# hs-64-spi_rev1_0.net
KiCad netlist of a schematic drawn in EAGLE
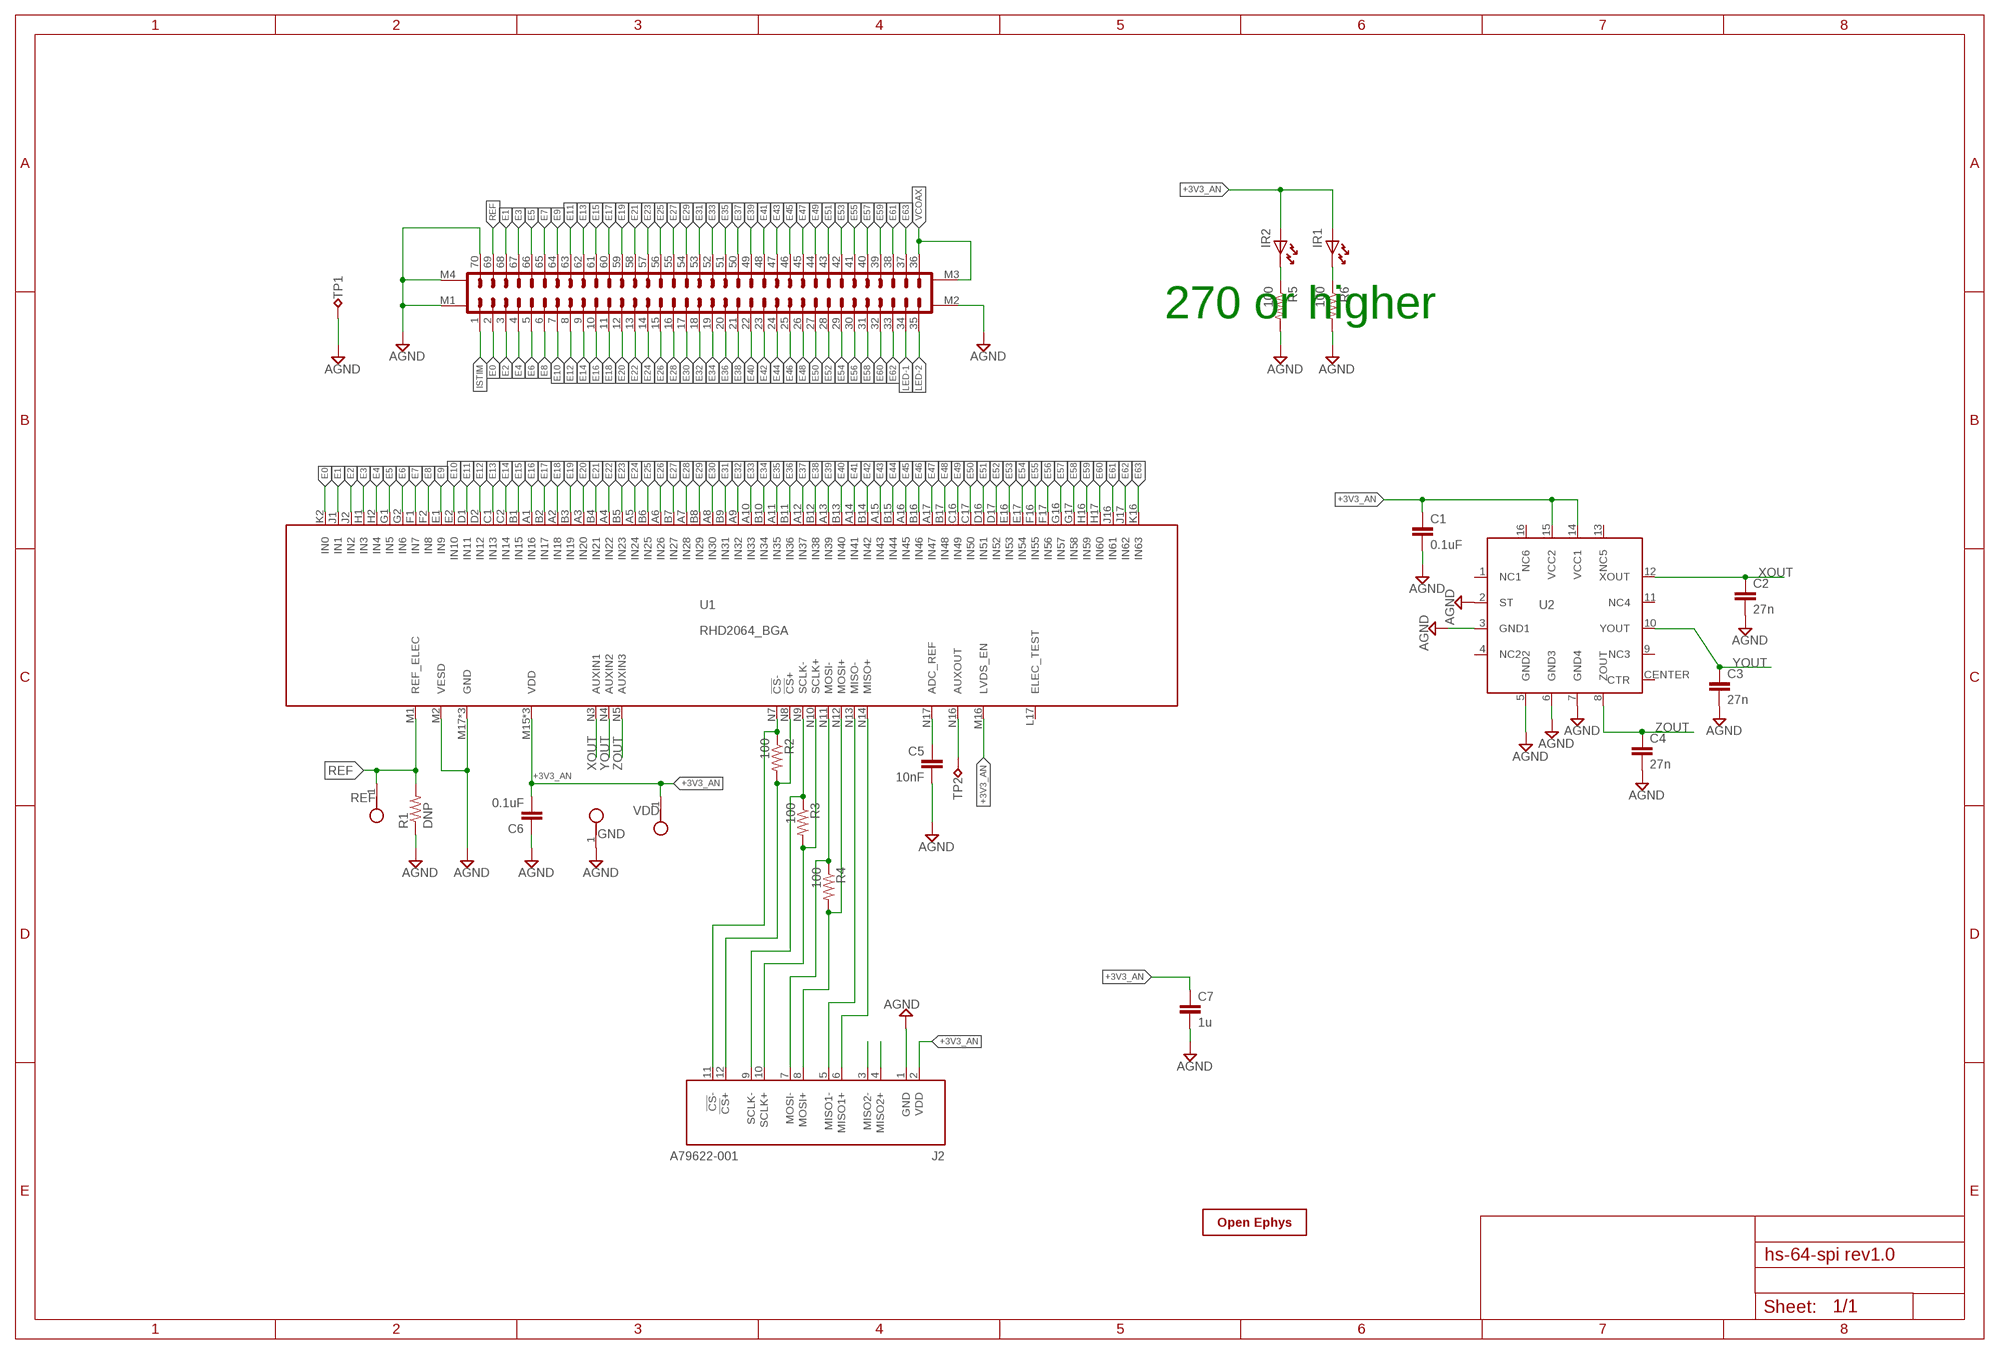
[diagram p0: schematic, sheet 1]

(export (version "E")
  (design (tool "Eeschema 10.0.6"))
  (components
    (comp (ref "C1")
      (value "0.1uF")
      (footprint "eagle-import:0402")
      (libsource (lib "eagle-import") (part "C_0402"))
    )
    (comp (ref "C2")
      (value "27n")
      (footprint "eagle-import:0402")
      (libsource (lib "eagle-import") (part "C_0402"))
    )
    (comp (ref "C3")
      (value "27n")
      (footprint "eagle-import:0402")
      (libsource (lib "eagle-import") (part "C_0402"))
    )
    (comp (ref "C4")
      (value "27n")
      (footprint "eagle-import:0402")
      (libsource (lib "eagle-import") (part "C_0402"))
    )
    (comp (ref "C5")
      (value "10nF")
      (footprint "eagle-import:0402T")
      (fields (field (name "PARTNO") "GRM033R71E103KE14D"))
      (libsource (lib "eagle-import") (part "C_0402T"))
    )
    (comp (ref "C6")
      (value "0.1uF")
      (footprint "eagle-import:0402T")
      (libsource (lib "eagle-import") (part "C_0402T"))
    )
    (comp (ref "C7")
      (value "1u")
      (footprint "eagle-import:0402")
      (libsource (lib "eagle-import") (part "C_0402"))
    )
    (comp (ref "GND")
      (value "TESTPOINT_SMALL")
      (footprint "eagle-import:TESTPOINT_SMALL")
      (libsource (lib "eagle-import") (part "TESTPOINT_SMALL"))
    )
    (comp (ref "IR1")
      (value "LEDHAND")
      (footprint "eagle-import:LED_HAND")
      (libsource (lib "eagle-import") (part "LEDHAND"))
    )
    (comp (ref "IR2")
      (value "LEDHAND")
      (footprint "eagle-import:LED_HAND")
      (libsource (lib "eagle-import") (part "LEDHAND"))
    )
    (comp (ref "J1")
      (value "DF40C-70DP-0.4V(51)")
      (footprint "eagle-import:DF40-70HEAD-LESS-SILK")
      (libsource (lib "eagle-import") (part "PINHD-2X35+4DF40-70HEAD-LESS-SILK"))
    )
    (comp (ref "J2")
      (value "A79622-001")
      (footprint "eagle-import:A79622-001")
      (libsource (lib "eagle-import") (part "A79622-001"))
    )
    (comp (ref "R1")
      (value "DNP")
      (footprint "eagle-import:0603")
      (fields (field (name "MPN") "ERJ-3EKFxxxxV"))
      (libsource (lib "eagle-import") (part "R_0603"))
    )
    (comp (ref "R2")
      (value "100")
      (footprint "eagle-import:0402")
      (libsource (lib "eagle-import") (part "R_0402"))
    )
    (comp (ref "R3")
      (value "100")
      (footprint "eagle-import:0402")
      (libsource (lib "eagle-import") (part "R_0402"))
    )
    (comp (ref "R4")
      (value "100")
      (footprint "eagle-import:0402")
      (libsource (lib "eagle-import") (part "R_0402"))
    )
    (comp (ref "R5")
      (value "100")
      (footprint "eagle-import:0402")
      (libsource (lib "eagle-import") (part "R_0402"))
    )
    (comp (ref "R6")
      (value "100")
      (footprint "eagle-import:0402")
      (libsource (lib "eagle-import") (part "R_0402"))
    )
    (comp (ref "REF")
      (value "TESTPOINT_SMALL")
      (footprint "eagle-import:TESTPOINT_SMALL")
      (libsource (lib "eagle-import") (part "TESTPOINT_SMALL"))
    )
    (comp (ref "TP1")
      (value "VCC")
      (footprint "eagle-import:TP07R")
      (libsource (lib "eagle-import") (part "TPTP07R"))
    )
    (comp (ref "TP2")
      (value "VCC")
      (footprint "eagle-import:TP07R")
      (libsource (lib "eagle-import") (part "TPTP07R"))
    )
    (comp (ref "U1")
      (value "RHD2064_BGA")
      (footprint "eagle-import:BGA104_0.5MM")
      (libsource (lib "eagle-import") (part "RHD2164_BGA_BGA"))
    )
    (comp (ref "U2")
      (value "ADXL335_IDAX")
      (footprint "eagle-import:ADXL335_IDAX")
      (libsource (lib "eagle-import") (part "ADXL335_IDAX"))
    )
    (comp (ref "VDD")
      (value "TESTPOINT_SMALL")
      (footprint "eagle-import:TESTPOINT_SMALL")
      (libsource (lib "eagle-import") (part "TESTPOINT_SMALL"))
    )
    (comp (ref "X")
      (value "OE-LOGO_3.5X2.5")
      (footprint "eagle-import:OE-LOGO-3.5X2.5")
      (libsource (lib "eagle-import") (part "OE-LOGO_3.5X2.5"))
    )
  )
  (nets
    (net (code "1") (name "+3V3_AN") (class "Default")
      (node (ref "C1") (pin "1") (pinfunction "1_1") (pintype "passive"))
      (node (ref "C6") (pin "2") (pinfunction "2_2") (pintype "passive"))
      (node (ref "C7") (pin "1") (pinfunction "1_1") (pintype "passive"))
      (node (ref "IR1") (pin "A") (pinfunction "A_A") (pintype "bidirectional"))
      (node (ref "IR2") (pin "A") (pinfunction "A_A") (pintype "bidirectional"))
      (node (ref "J2") (pin "2") (pinfunction "VDD_2") (pintype "bidirectional"))
      (node (ref "U1") (pin "M15") (pinfunction "VDD_M15") (pintype "power_in"))
      (node (ref "U1") (pin "M16") (pinfunction "LVDS_EN_M16") (pintype "input"))
      (node (ref "U1") (pin "N15") (pinfunction "VDD_N15") (pintype "power_in"))
      (node (ref "U1") (pin "N2") (pinfunction "VDD_N2") (pintype "power_in"))
      (node (ref "U2") (pin "14") (pinfunction "VCC1_14") (pintype "power_in"))
      (node (ref "U2") (pin "15") (pinfunction "VCC2_15") (pintype "power_in"))
      (node (ref "VDD") (pin "1") (pinfunction "1_1") (pintype "passive"))
    )
    (net (code "2") (name "/XOUT") (class "Default")
      (node (ref "C2") (pin "1") (pinfunction "1_1") (pintype "passive"))
      (node (ref "U1") (pin "N3") (pinfunction "AUXIN1_N3") (pintype "input"))
      (node (ref "U2") (pin "12") (pinfunction "XOUT_12") (pintype "output"))
    )
    (net (code "3") (name "/YOUT") (class "Default")
      (node (ref "C3") (pin "1") (pinfunction "1_1") (pintype "passive"))
      (node (ref "U1") (pin "N4") (pinfunction "AUXIN2_N4") (pintype "input"))
      (node (ref "U2") (pin "10") (pinfunction "YOUT_10") (pintype "output"))
    )
    (net (code "4") (name "/ZOUT") (class "Default")
      (node (ref "C4") (pin "1") (pinfunction "1_1") (pintype "passive"))
      (node (ref "U1") (pin "N5") (pinfunction "AUXIN3_N5") (pintype "input"))
      (node (ref "U2") (pin "8") (pinfunction "ZOUT_8") (pintype "output"))
    )
    (net (code "5") (name "AGND") (class "Default")
      (node (ref "C1") (pin "2") (pinfunction "2_2") (pintype "passive"))
      (node (ref "C2") (pin "2") (pinfunction "2_2") (pintype "passive"))
      (node (ref "C3") (pin "2") (pinfunction "2_2") (pintype "passive"))
      (node (ref "C4") (pin "2") (pinfunction "2_2") (pintype "passive"))
      (node (ref "C5") (pin "2") (pinfunction "2_2") (pintype "passive"))
      (node (ref "C6") (pin "1") (pinfunction "1_1") (pintype "passive"))
      (node (ref "C7") (pin "2") (pinfunction "2_2") (pintype "passive"))
      (node (ref "GND") (pin "1") (pinfunction "1_1") (pintype "passive"))
      (node (ref "J1") (pin "70") (pinfunction "70_70") (pintype "bidirectional"))
      (node (ref "J1") (pin "M1") (pinfunction "M1_M1") (pintype "bidirectional"))
      (node (ref "J1") (pin "M2") (pinfunction "M2_M2") (pintype "bidirectional"))
      (node (ref "J1") (pin "M4") (pinfunction "M4_M4") (pintype "bidirectional"))
      (node (ref "J2") (pin "1") (pinfunction "GND_1") (pintype "power_in"))
      (node (ref "R1") (pin "1") (pinfunction "1_1") (pintype "passive"))
      (node (ref "R5") (pin "2") (pinfunction "2_2") (pintype "passive"))
      (node (ref "R6") (pin "2") (pinfunction "2_2") (pintype "passive"))
      (node (ref "TP1") (pin "TP") (pinfunction "TP_TP") (pintype "bidirectional"))
      (node (ref "U1") (pin "M17") (pinfunction "GND_M17") (pintype "power_in"))
      (node (ref "U1") (pin "M2") (pinfunction "VESD_M2") (pintype "power_in"))
      (node (ref "U1") (pin "N1") (pinfunction "GND_N1") (pintype "power_in"))
      (node (ref "U1") (pin "N6") (pinfunction "GND_N6") (pintype "power_in"))
      (node (ref "U2") (pin "2") (pinfunction "ST_2") (pintype "input"))
      (node (ref "U2") (pin "3") (pinfunction "GND1_3") (pintype "power_in"))
      (node (ref "U2") (pin "5") (pinfunction "GND2_5") (pintype "power_in"))
      (node (ref "U2") (pin "6") (pinfunction "GND3_6") (pintype "power_in"))
      (node (ref "U2") (pin "7") (pinfunction "GND4_7") (pintype "power_in"))
    )
    (net (code "6") (name "E0") (class "Default")
      (node (ref "J1") (pin "2") (pinfunction "2_2") (pintype "bidirectional"))
      (node (ref "U1") (pin "K2") (pinfunction "IN0_K2") (pintype "input"))
    )
    (net (code "7") (name "E1") (class "Default")
      (node (ref "J1") (pin "68") (pinfunction "68_68") (pintype "bidirectional"))
      (node (ref "U1") (pin "J1") (pinfunction "IN1_J1") (pintype "input"))
    )
    (net (code "8") (name "E2") (class "Default")
      (node (ref "J1") (pin "3") (pinfunction "3_3") (pintype "bidirectional"))
      (node (ref "U1") (pin "J2") (pinfunction "IN2_J2") (pintype "input"))
    )
    (net (code "9") (name "E3") (class "Default")
      (node (ref "J1") (pin "67") (pinfunction "67_67") (pintype "bidirectional"))
      (node (ref "U1") (pin "H1") (pinfunction "IN3_H1") (pintype "input"))
    )
    (net (code "10") (name "E4") (class "Default")
      (node (ref "J1") (pin "4") (pinfunction "4_4") (pintype "bidirectional"))
      (node (ref "U1") (pin "H2") (pinfunction "IN4_H2") (pintype "input"))
    )
    (net (code "11") (name "E5") (class "Default")
      (node (ref "J1") (pin "66") (pinfunction "66_66") (pintype "bidirectional"))
      (node (ref "U1") (pin "G1") (pinfunction "IN5_G1") (pintype "input"))
    )
    (net (code "12") (name "E6") (class "Default")
      (node (ref "J1") (pin "5") (pinfunction "5_5") (pintype "bidirectional"))
      (node (ref "U1") (pin "G2") (pinfunction "IN6_G2") (pintype "input"))
    )
    (net (code "13") (name "E7") (class "Default")
      (node (ref "J1") (pin "65") (pinfunction "65_65") (pintype "bidirectional"))
      (node (ref "U1") (pin "F1") (pinfunction "IN7_F1") (pintype "input"))
    )
    (net (code "14") (name "E8") (class "Default")
      (node (ref "J1") (pin "6") (pinfunction "6_6") (pintype "bidirectional"))
      (node (ref "U1") (pin "F2") (pinfunction "IN8_F2") (pintype "input"))
    )
    (net (code "15") (name "E9") (class "Default")
      (node (ref "J1") (pin "64") (pinfunction "64_64") (pintype "bidirectional"))
      (node (ref "U1") (pin "E1") (pinfunction "IN9_E1") (pintype "input"))
    )
    (net (code "16") (name "E10") (class "Default")
      (node (ref "J1") (pin "7") (pinfunction "7_7") (pintype "bidirectional"))
      (node (ref "U1") (pin "E2") (pinfunction "IN10_E2") (pintype "input"))
    )
    (net (code "17") (name "E11") (class "Default")
      (node (ref "J1") (pin "63") (pinfunction "63_63") (pintype "bidirectional"))
      (node (ref "U1") (pin "D1") (pinfunction "IN11_D1") (pintype "input"))
    )
    (net (code "18") (name "E12") (class "Default")
      (node (ref "J1") (pin "8") (pinfunction "8_8") (pintype "bidirectional"))
      (node (ref "U1") (pin "D2") (pinfunction "IN12_D2") (pintype "input"))
    )
    (net (code "19") (name "E13") (class "Default")
      (node (ref "J1") (pin "62") (pinfunction "62_62") (pintype "bidirectional"))
      (node (ref "U1") (pin "C1") (pinfunction "IN13_C1") (pintype "input"))
    )
    (net (code "20") (name "E14") (class "Default")
      (node (ref "J1") (pin "9") (pinfunction "9_9") (pintype "bidirectional"))
      (node (ref "U1") (pin "C2") (pinfunction "IN14_C2") (pintype "input"))
    )
    (net (code "21") (name "E15") (class "Default")
      (node (ref "J1") (pin "61") (pinfunction "61_61") (pintype "bidirectional"))
      (node (ref "U1") (pin "B1") (pinfunction "IN15_B1") (pintype "input"))
    )
    (net (code "22") (name "E16") (class "Default")
      (node (ref "J1") (pin "10") (pinfunction "10_10") (pintype "bidirectional"))
      (node (ref "U1") (pin "A1") (pinfunction "IN16_A1") (pintype "input"))
    )
    (net (code "23") (name "E17") (class "Default")
      (node (ref "J1") (pin "60") (pinfunction "60_60") (pintype "bidirectional"))
      (node (ref "U1") (pin "B2") (pinfunction "IN17_B2") (pintype "input"))
    )
    (net (code "24") (name "E18") (class "Default")
      (node (ref "J1") (pin "11") (pinfunction "11_11") (pintype "bidirectional"))
      (node (ref "U1") (pin "A2") (pinfunction "IN18_A2") (pintype "input"))
    )
    (net (code "25") (name "E19") (class "Default")
      (node (ref "J1") (pin "59") (pinfunction "59_59") (pintype "bidirectional"))
      (node (ref "U1") (pin "B3") (pinfunction "IN19_B3") (pintype "input"))
    )
    (net (code "26") (name "E20") (class "Default")
      (node (ref "J1") (pin "12") (pinfunction "12_12") (pintype "bidirectional"))
      (node (ref "U1") (pin "A3") (pinfunction "IN20_A3") (pintype "input"))
    )
    (net (code "27") (name "E21") (class "Default")
      (node (ref "J1") (pin "58") (pinfunction "58_58") (pintype "bidirectional"))
      (node (ref "U1") (pin "B4") (pinfunction "IN21_B4") (pintype "input"))
    )
    (net (code "28") (name "E22") (class "Default")
      (node (ref "J1") (pin "13") (pinfunction "13_13") (pintype "bidirectional"))
      (node (ref "U1") (pin "A4") (pinfunction "IN22_A4") (pintype "input"))
    )
    (net (code "29") (name "E23") (class "Default")
      (node (ref "J1") (pin "57") (pinfunction "57_57") (pintype "bidirectional"))
      (node (ref "U1") (pin "B5") (pinfunction "IN23_B5") (pintype "input"))
    )
    (net (code "30") (name "E24") (class "Default")
      (node (ref "J1") (pin "14") (pinfunction "14_14") (pintype "bidirectional"))
      (node (ref "U1") (pin "A5") (pinfunction "IN24_A5") (pintype "input"))
    )
    (net (code "31") (name "E25") (class "Default")
      (node (ref "J1") (pin "56") (pinfunction "56_56") (pintype "bidirectional"))
      (node (ref "U1") (pin "B6") (pinfunction "IN25_B6") (pintype "input"))
    )
    (net (code "32") (name "E26") (class "Default")
      (node (ref "J1") (pin "15") (pinfunction "15_15") (pintype "bidirectional"))
      (node (ref "U1") (pin "A6") (pinfunction "IN26_A6") (pintype "input"))
    )
    (net (code "33") (name "E27") (class "Default")
      (node (ref "J1") (pin "55") (pinfunction "55_55") (pintype "bidirectional"))
      (node (ref "U1") (pin "B7") (pinfunction "IN27_B7") (pintype "input"))
    )
    (net (code "34") (name "E28") (class "Default")
      (node (ref "J1") (pin "16") (pinfunction "16_16") (pintype "bidirectional"))
      (node (ref "U1") (pin "A7") (pinfunction "IN28_A7") (pintype "input"))
    )
    (net (code "35") (name "E29") (class "Default")
      (node (ref "J1") (pin "54") (pinfunction "54_54") (pintype "bidirectional"))
      (node (ref "U1") (pin "B8") (pinfunction "IN29_B8") (pintype "input"))
    )
    (net (code "36") (name "E30") (class "Default")
      (node (ref "J1") (pin "17") (pinfunction "17_17") (pintype "bidirectional"))
      (node (ref "U1") (pin "A8") (pinfunction "IN30_A8") (pintype "input"))
    )
    (net (code "37") (name "E31") (class "Default")
      (node (ref "J1") (pin "53") (pinfunction "53_53") (pintype "bidirectional"))
      (node (ref "U1") (pin "B9") (pinfunction "IN31_B9") (pintype "input"))
    )
    (net (code "38") (name "E32") (class "Default")
      (node (ref "J1") (pin "18") (pinfunction "18_18") (pintype "bidirectional"))
      (node (ref "U1") (pin "A9") (pinfunction "IN32_A9") (pintype "input"))
    )
    (net (code "39") (name "E33") (class "Default")
      (node (ref "J1") (pin "52") (pinfunction "52_52") (pintype "bidirectional"))
      (node (ref "U1") (pin "A10") (pinfunction "IN33_A10") (pintype "input"))
    )
    (net (code "40") (name "E34") (class "Default")
      (node (ref "J1") (pin "19") (pinfunction "19_19") (pintype "bidirectional"))
      (node (ref "U1") (pin "B10") (pinfunction "IN34_B10") (pintype "input"))
    )
    (net (code "41") (name "E35") (class "Default")
      (node (ref "J1") (pin "51") (pinfunction "51_51") (pintype "bidirectional"))
      (node (ref "U1") (pin "A11") (pinfunction "IN35_A11") (pintype "input"))
    )
    (net (code "42") (name "E36") (class "Default")
      (node (ref "J1") (pin "20") (pinfunction "20_20") (pintype "bidirectional"))
      (node (ref "U1") (pin "B11") (pinfunction "IN36_B11") (pintype "input"))
    )
    (net (code "43") (name "E37") (class "Default")
      (node (ref "J1") (pin "50") (pinfunction "50_50") (pintype "bidirectional"))
      (node (ref "U1") (pin "A12") (pinfunction "IN37_A12") (pintype "input"))
    )
    (net (code "44") (name "E38") (class "Default")
      (node (ref "J1") (pin "21") (pinfunction "21_21") (pintype "bidirectional"))
      (node (ref "U1") (pin "B12") (pinfunction "IN38_B12") (pintype "input"))
    )
    (net (code "45") (name "E39") (class "Default")
      (node (ref "J1") (pin "49") (pinfunction "49_49") (pintype "bidirectional"))
      (node (ref "U1") (pin "A13") (pinfunction "IN39_A13") (pintype "input"))
    )
    (net (code "46") (name "E40") (class "Default")
      (node (ref "J1") (pin "22") (pinfunction "22_22") (pintype "bidirectional"))
      (node (ref "U1") (pin "B13") (pinfunction "IN40_B13") (pintype "input"))
    )
    (net (code "47") (name "E41") (class "Default")
      (node (ref "J1") (pin "48") (pinfunction "48_48") (pintype "bidirectional"))
      (node (ref "U1") (pin "A14") (pinfunction "IN41_A14") (pintype "input"))
    )
    (net (code "48") (name "E42") (class "Default")
      (node (ref "J1") (pin "23") (pinfunction "23_23") (pintype "bidirectional"))
      (node (ref "U1") (pin "B14") (pinfunction "IN42_B14") (pintype "input"))
    )
    (net (code "49") (name "E43") (class "Default")
      (node (ref "J1") (pin "47") (pinfunction "47_47") (pintype "bidirectional"))
      (node (ref "U1") (pin "A15") (pinfunction "IN43_A15") (pintype "input"))
    )
    (net (code "50") (name "E44") (class "Default")
      (node (ref "J1") (pin "24") (pinfunction "24_24") (pintype "bidirectional"))
      (node (ref "U1") (pin "B15") (pinfunction "IN44_B15") (pintype "input"))
    )
    (net (code "51") (name "E45") (class "Default")
      (node (ref "J1") (pin "46") (pinfunction "46_46") (pintype "bidirectional"))
      (node (ref "U1") (pin "A16") (pinfunction "IN45_A16") (pintype "input"))
    )
    (net (code "52") (name "E46") (class "Default")
      (node (ref "J1") (pin "25") (pinfunction "25_25") (pintype "bidirectional"))
      (node (ref "U1") (pin "B16") (pinfunction "IN46_B16") (pintype "input"))
    )
    (net (code "53") (name "E47") (class "Default")
      (node (ref "J1") (pin "45") (pinfunction "45_45") (pintype "bidirectional"))
      (node (ref "U1") (pin "A17") (pinfunction "IN47_A17") (pintype "input"))
    )
    (net (code "54") (name "E48") (class "Default")
      (node (ref "J1") (pin "26") (pinfunction "26_26") (pintype "bidirectional"))
      (node (ref "U1") (pin "B17") (pinfunction "IN48_B17") (pintype "input"))
    )
    (net (code "55") (name "E49") (class "Default")
      (node (ref "J1") (pin "44") (pinfunction "44_44") (pintype "bidirectional"))
      (node (ref "U1") (pin "C16") (pinfunction "IN49_C16") (pintype "input"))
    )
    (net (code "56") (name "E50") (class "Default")
      (node (ref "J1") (pin "27") (pinfunction "27_27") (pintype "bidirectional"))
      (node (ref "U1") (pin "C17") (pinfunction "IN50_C17") (pintype "input"))
    )
    (net (code "57") (name "E51") (class "Default")
      (node (ref "J1") (pin "43") (pinfunction "43_43") (pintype "bidirectional"))
      (node (ref "U1") (pin "D16") (pinfunction "IN51_D16") (pintype "input"))
    )
    (net (code "58") (name "E52") (class "Default")
      (node (ref "J1") (pin "28") (pinfunction "28_28") (pintype "bidirectional"))
      (node (ref "U1") (pin "D17") (pinfunction "IN52_D17") (pintype "input"))
    )
    (net (code "59") (name "E53") (class "Default")
      (node (ref "J1") (pin "42") (pinfunction "42_42") (pintype "bidirectional"))
      (node (ref "U1") (pin "E16") (pinfunction "IN53_E16") (pintype "input"))
    )
    (net (code "60") (name "E54") (class "Default")
      (node (ref "J1") (pin "29") (pinfunction "29_29") (pintype "bidirectional"))
      (node (ref "U1") (pin "E17") (pinfunction "IN54_E17") (pintype "input"))
    )
    (net (code "61") (name "E55") (class "Default")
      (node (ref "J1") (pin "41") (pinfunction "41_41") (pintype "bidirectional"))
      (node (ref "U1") (pin "F16") (pinfunction "IN55_F16") (pintype "input"))
    )
    (net (code "62") (name "E56") (class "Default")
      (node (ref "J1") (pin "30") (pinfunction "30_30") (pintype "bidirectional"))
      (node (ref "U1") (pin "F17") (pinfunction "IN56_F17") (pintype "input"))
    )
    (net (code "63") (name "E57") (class "Default")
      (node (ref "J1") (pin "40") (pinfunction "40_40") (pintype "bidirectional"))
      (node (ref "U1") (pin "G16") (pinfunction "IN57_G16") (pintype "input"))
    )
    (net (code "64") (name "E58") (class "Default")
      (node (ref "J1") (pin "31") (pinfunction "31_31") (pintype "bidirectional"))
      (node (ref "U1") (pin "G17") (pinfunction "IN58_G17") (pintype "input"))
    )
    (net (code "65") (name "E59") (class "Default")
      (node (ref "J1") (pin "39") (pinfunction "39_39") (pintype "bidirectional"))
      (node (ref "U1") (pin "H16") (pinfunction "IN59_H16") (pintype "input"))
    )
    (net (code "66") (name "E60") (class "Default")
      (node (ref "J1") (pin "32") (pinfunction "32_32") (pintype "bidirectional"))
      (node (ref "U1") (pin "H17") (pinfunction "IN60_H17") (pintype "input"))
    )
    (net (code "67") (name "E61") (class "Default")
      (node (ref "J1") (pin "38") (pinfunction "38_38") (pintype "bidirectional"))
      (node (ref "U1") (pin "J16") (pinfunction "IN61_J16") (pintype "input"))
    )
    (net (code "68") (name "E62") (class "Default")
      (node (ref "J1") (pin "33") (pinfunction "33_33") (pintype "bidirectional"))
      (node (ref "U1") (pin "J17") (pinfunction "IN62_J17") (pintype "input"))
    )
    (net (code "69") (name "E63") (class "Default")
      (node (ref "J1") (pin "37") (pinfunction "37_37") (pintype "bidirectional"))
      (node (ref "U1") (pin "K16") (pinfunction "IN63_K16") (pintype "input"))
    )
    (net (code "70") (name "ISTIM") (class "Default")
      (node (ref "J1") (pin "1") (pinfunction "1_1") (pintype "bidirectional"))
    )
    (net (code "71") (name "LED-1") (class "Default")
      (node (ref "J1") (pin "34") (pinfunction "34_34") (pintype "bidirectional"))
    )
    (net (code "72") (name "LED-2") (class "Default")
      (node (ref "J1") (pin "35") (pinfunction "35_35") (pintype "bidirectional"))
    )
    (net (code "73") (name "Net-(IR1-PadK)") (class "Default")
      (node (ref "IR1") (pin "K") (pinfunction "K_K") (pintype "bidirectional"))
      (node (ref "R6") (pin "1") (pinfunction "1_1") (pintype "passive"))
    )
    (net (code "74") (name "Net-(IR2-PadK)") (class "Default")
      (node (ref "IR2") (pin "K") (pinfunction "K_K") (pintype "bidirectional"))
      (node (ref "R5") (pin "1") (pinfunction "1_1") (pintype "passive"))
    )
    (net (code "75") (name "Net-(J2-MISO1+)") (class "Default")
      (node (ref "J2") (pin "6") (pinfunction "MISO1+_6") (pintype "bidirectional"))
      (node (ref "U1") (pin "N14") (pinfunction "MISO+_N14") (pintype "output"))
    )
    (net (code "76") (name "Net-(J2-MISO1-)") (class "Default")
      (node (ref "J2") (pin "5") (pinfunction "MISO1-_5") (pintype "bidirectional"))
      (node (ref "U1") (pin "N13") (pinfunction "MISO-_N13") (pintype "output"))
    )
    (net (code "77") (name "Net-(J2-MOSI+)") (class "Default")
      (node (ref "J2") (pin "8") (pinfunction "MOSI+_8") (pintype "bidirectional"))
      (node (ref "R4") (pin "2") (pinfunction "2_2") (pintype "passive"))
      (node (ref "U1") (pin "N12") (pinfunction "MOSI+_N12") (pintype "input"))
    )
    (net (code "78") (name "Net-(J2-MOSI-)") (class "Default")
      (node (ref "J2") (pin "7") (pinfunction "MOSI-_7") (pintype "bidirectional"))
      (node (ref "R4") (pin "1") (pinfunction "1_1") (pintype "passive"))
      (node (ref "U1") (pin "N11") (pinfunction "MOSI-_N11") (pintype "input"))
    )
    (net (code "79") (name "Net-(J2-SCLK+)") (class "Default")
      (node (ref "J2") (pin "10") (pinfunction "SCLK+_10") (pintype "bidirectional"))
      (node (ref "R3") (pin "2") (pinfunction "2_2") (pintype "passive"))
      (node (ref "U1") (pin "N10") (pinfunction "SCLK+_N10") (pintype "input"))
    )
    (net (code "80") (name "Net-(J2-SCLK-)") (class "Default")
      (node (ref "J2") (pin "9") (pinfunction "SCLK-_9") (pintype "bidirectional"))
      (node (ref "R3") (pin "1") (pinfunction "1_1") (pintype "passive"))
      (node (ref "U1") (pin "N9") (pinfunction "SCLK-_N9") (pintype "input"))
    )
    (net (code "81") (name "Net-(J2-~{CS}+)") (class "Default")
      (node (ref "J2") (pin "12") (pinfunction "~{CS}+_12") (pintype "bidirectional"))
      (node (ref "R2") (pin "2") (pinfunction "2_2") (pintype "passive"))
      (node (ref "U1") (pin "N8") (pinfunction "~{CS}+_N8") (pintype "input"))
    )
    (net (code "82") (name "Net-(J2-~{CS}-)") (class "Default")
      (node (ref "J2") (pin "11") (pinfunction "~{CS}-_11") (pintype "bidirectional"))
      (node (ref "R2") (pin "1") (pinfunction "1_1") (pintype "passive"))
      (node (ref "U1") (pin "N7") (pinfunction "~{CS}-_N7") (pintype "input"))
    )
    (net (code "83") (name "Net-(U1-ADC_REF)") (class "Default")
      (node (ref "C5") (pin "1") (pinfunction "1_1") (pintype "passive"))
      (node (ref "U1") (pin "N17") (pinfunction "ADC_REF_N17") (pintype "passive"))
    )
    (net (code "84") (name "Net-(U1-AUXOUT)") (class "Default")
      (node (ref "TP2") (pin "TP") (pinfunction "TP_TP") (pintype "bidirectional"))
      (node (ref "U1") (pin "N16") (pinfunction "AUXOUT_N16") (pintype "tri_state"))
    )
    (net (code "85") (name "REF") (class "Default")
      (node (ref "J1") (pin "69") (pinfunction "69_69") (pintype "bidirectional"))
      (node (ref "R1") (pin "2") (pinfunction "2_2") (pintype "passive"))
      (node (ref "REF") (pin "1") (pinfunction "1_1") (pintype "passive"))
      (node (ref "U1") (pin "M1") (pinfunction "REF_ELEC_M1") (pintype "input"))
    )
    (net (code "86") (name "VCOAX") (class "Default")
      (node (ref "J1") (pin "36") (pinfunction "36_36") (pintype "bidirectional"))
      (node (ref "J1") (pin "M3") (pinfunction "M3_M3") (pintype "bidirectional"))
    )
    (net (code "87") (name "unconnected-(J2-MISO2+-Pad4)") (class "Default")
      (node (ref "J2") (pin "4") (pinfunction "MISO2+_4") (pintype "bidirectional"))
    )
    (net (code "88") (name "unconnected-(J2-MISO2--Pad3)") (class "Default")
      (node (ref "J2") (pin "3") (pinfunction "MISO2-_3") (pintype "bidirectional"))
    )
    (net (code "89") (name "unconnected-(U1-ELEC_TEST-PadL17)") (class "Default")
      (node (ref "U1") (pin "L17") (pinfunction "ELEC_TEST_L17") (pintype "input"))
    )
    (net (code "90") (name "unconnected-(U2-CTR-PadCENTER)") (class "Default")
      (node (ref "U2") (pin "CENTER") (pinfunction "CTR_CENTER") (pintype "passive"))
    )
    (net (code "91") (name "unconnected-(U2-NC1-Pad1)") (class "Default")
      (node (ref "U2") (pin "1") (pinfunction "NC1_1") (pintype "no_connect"))
    )
    (net (code "92") (name "unconnected-(U2-NC2-Pad4)") (class "Default")
      (node (ref "U2") (pin "4") (pinfunction "NC2_4") (pintype "no_connect"))
    )
    (net (code "93") (name "unconnected-(U2-NC3-Pad9)") (class "Default")
      (node (ref "U2") (pin "9") (pinfunction "NC3_9") (pintype "no_connect"))
    )
    (net (code "94") (name "unconnected-(U2-NC4-Pad11)") (class "Default")
      (node (ref "U2") (pin "11") (pinfunction "NC4_11") (pintype "no_connect"))
    )
    (net (code "95") (name "unconnected-(U2-NC5-Pad13)") (class "Default")
      (node (ref "U2") (pin "13") (pinfunction "NC5_13") (pintype "no_connect"))
    )
    (net (code "96") (name "unconnected-(U2-NC6-Pad16)") (class "Default")
      (node (ref "U2") (pin "16") (pinfunction "NC6_16") (pintype "no_connect"))
    )
  )
)
